# AVR-programming-cable.net
KiCad netlist of a schematic drawn in Altium Designer
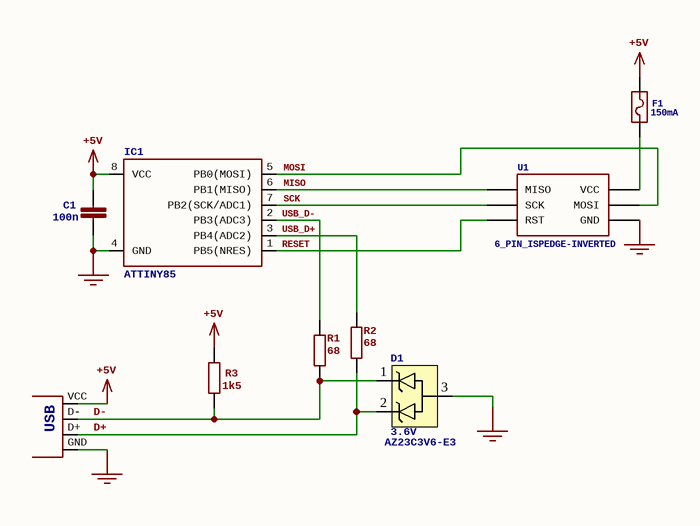
[diagram p0: AVR-programming-cable.SchDoc]

(export (version "E")
  (design (tool "Eeschema 10.0.6"))
  (components
    (comp (ref "C1")
      (value "100n")
      (footprint "RESC0805(2012)_M")
      (description "CAPACITOR, European symbol")
      (libsource (lib "p.peter-rcl") (part "C-EUC0603"))
    )
    (comp (ref "D1")
      (value "3.6V")
      (footprint "SOT23_M")
      (description "3.6V Zener Diode, Dual Common Anode")
      (fields (field (name "MPN") "AZ23C3V6-E3") (field (name "MANUFACTURER") "Vishay Semi"))
      (libsource (lib "v1") (part "DUAL_ZENER"))
    )
    (comp (ref "F1")
      (value "150mA")
      (footprint "SMD-0805")
      (libsource (lib "p.peter-regulators") (part "FUSE0805"))
    )
    (comp (ref "IC1")
      (value "ATTINY85")
      (footprint "8P3")
      (description "Atmel ATTiny45")
      (libsource (lib "SparkFun") (part "ATTINY45"))
    )
    (comp (ref "R1")
      (value "68")
      (footprint "RESC0805(2012)_M")
      (description "RESISTOR, European symbol")
      (libsource (lib "p.peter-rcl") (part "R-EU_R0603"))
    )
    (comp (ref "R2")
      (value "68")
      (footprint "RESC0805(2012)_M")
      (description "RESISTOR, European symbol")
      (libsource (lib "p.peter-rcl") (part "R-EU_R0603"))
    )
    (comp (ref "R3")
      (value "1k5")
      (footprint "RESC0805(2012)_M")
      (description "RESISTOR, European symbol")
      (libsource (lib "p.peter-rcl") (part "R-EU_R0603"))
    )
    (comp (ref "U$2")
      (value "USB2.5-2.0-2.5")
      (footprint "USB-FEMALE-A")
      (fields (field (name "USB") "USB"))
      (libsource (lib "p.peter-connectors") (part "USB2.5-2.0-2.5"))
    )
    (comp (ref "U1")
      (value "6_PIN_ISPEDGE-INVERTED")
      (footprint "6_PIN_EDGE")
      (description "AVR 6 PIN ISP header Edge connector normal layout")
      (libsource (lib "ppeter") (part "6_PIN_ISPEDGE-INVERTED"))
    )
  )
  (nets
    (net (code "1") (name "+5V") (class "Default")
      (node (ref "C1") (pin "1") (pinfunction "1_1") (pintype "passive"))
      (node (ref "F1") (pin "2") (pinfunction "P$2_2") (pintype "passive"))
      (node (ref "IC1") (pin "8") (pinfunction "VCC_8") (pintype "passive"))
      (node (ref "R3") (pin "2") (pinfunction "2_2") (pintype "passive"))
      (node (ref "U$2") (pin "VCC") (pinfunction "VBUS_VCC") (pintype "passive"))
    )
    (net (code "2") (name "/D+") (class "Default")
      (node (ref "D1") (pin "2") (pinfunction "2_2") (pintype "passive"))
      (node (ref "R2") (pin "1") (pinfunction "1_1") (pintype "passive"))
      (node (ref "U$2") (pin "D+") (pinfunction "D+_D+") (pintype "passive"))
    )
    (net (code "3") (name "/D-") (class "Default")
      (node (ref "D1") (pin "1") (pinfunction "1_1") (pintype "passive"))
      (node (ref "R1") (pin "1") (pinfunction "1_1") (pintype "passive"))
      (node (ref "R3") (pin "1") (pinfunction "1_1") (pintype "passive"))
      (node (ref "U$2") (pin "D-") (pinfunction "D-_D-") (pintype "passive"))
    )
    (net (code "4") (name "/MISO") (class "Default")
      (node (ref "IC1") (pin "6") (pinfunction "PB1(MISO)_6") (pintype "passive"))
      (node (ref "U1") (pin "2") (pinfunction "MISO_2") (pintype "passive"))
    )
    (net (code "5") (name "/MOSI") (class "Default")
      (node (ref "IC1") (pin "5") (pinfunction "PB0(MOSI)_5") (pintype "passive"))
      (node (ref "U1") (pin "3") (pinfunction "MOSI_3") (pintype "passive"))
    )
    (net (code "6") (name "/RESET") (class "Default")
      (node (ref "IC1") (pin "1") (pinfunction "PB5(NRES)_1") (pintype "passive"))
      (node (ref "U1") (pin "6") (pinfunction "RST_6") (pintype "passive"))
    )
    (net (code "7") (name "/SCK") (class "Default")
      (node (ref "IC1") (pin "7") (pinfunction "PB2(SCK/ADC1)_7") (pintype "passive"))
      (node (ref "U1") (pin "4") (pinfunction "SCK_4") (pintype "passive"))
    )
    (net (code "8") (name "/USB_D+") (class "Default")
      (node (ref "IC1") (pin "3") (pinfunction "PB4(ADC2)_3") (pintype "passive"))
      (node (ref "R2") (pin "2") (pinfunction "2_2") (pintype "passive"))
    )
    (net (code "9") (name "/USB_D-") (class "Default")
      (node (ref "IC1") (pin "2") (pinfunction "PB3(ADC3)_2") (pintype "passive"))
      (node (ref "R1") (pin "2") (pinfunction "2_2") (pintype "passive"))
    )
    (net (code "10") (name "GND") (class "Default")
      (node (ref "C1") (pin "2") (pinfunction "2_2") (pintype "passive"))
      (node (ref "D1") (pin "3") (pinfunction "3_3") (pintype "passive"))
      (node (ref "IC1") (pin "4") (pinfunction "GND_4") (pintype "passive"))
      (node (ref "U$2") (pin "GND") (pinfunction "GND_GND") (pintype "passive"))
      (node (ref "U1") (pin "5") (pinfunction "GND_5") (pintype "power_in"))
    )
    (net (code "11") (name "Net-(F1-P$1)") (class "Default")
      (node (ref "F1") (pin "1") (pinfunction "P$1_1") (pintype "passive"))
      (node (ref "U1") (pin "1") (pinfunction "VCC_1") (pintype "power_in"))
    )
  )
)
